# Fuente.net
KiCad netlist of a schematic drawn in Altium Designer
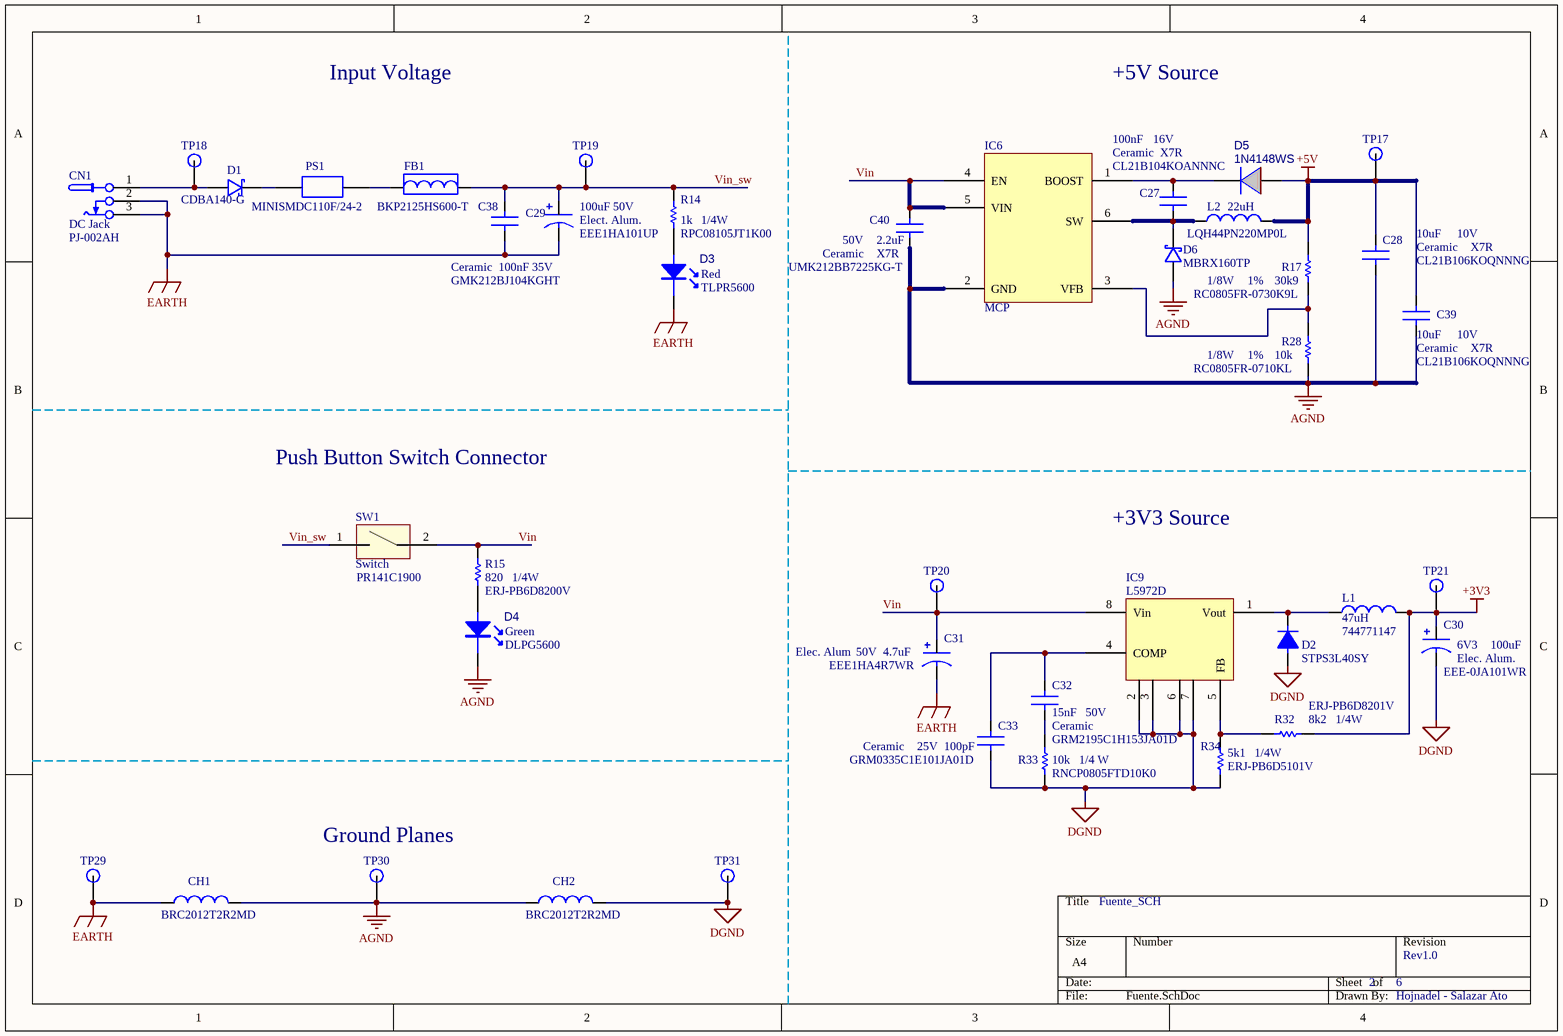
[diagram p0: Fuente.SchDoc]

(export (version "E")
  (design (tool "Eeschema 10.0.6"))
  (components
    (comp (ref "C27")
      (value "100nF 16V X7R")
      (footprint "C_0805")
      (description "Capacitor")
      (fields
        (field (name "C") "100nF")
        (field (name "V") "16V")
        (field (name "PART NUMBER") "CL21B104KOANNNC")
        (field (name "MATERIAL") "Ceramic")
        (field (name "COEF. TERM.") "X7R")
      )
      (libsource (lib "TDII_Lib_V2") (part "Cap1"))
    )
    (comp (ref "C28")
      (value "10uF 10V X7R")
      (footprint "C_0805")
      (description "Capacitor")
      (fields
        (field (name "C") "10uF")
        (field (name "V") "10V")
        (field (name "PART NUMBER") "CL21B106KOQNNNG")
        (field (name "MATERIAL") "Ceramic")
        (field (name "COEF. TERM.") "X7R")
      )
      (libsource (lib "TDII_Lib_V2") (part "Cap1"))
    )
    (comp (ref "C29")
      (value "100uF 50V ElecAlum")
      (footprint "C_AE10083X105M")
      (description "Capacitor")
      (fields
        (field (name "C") "100uF")
        (field (name "V") "50V")
        (field (name "MATERIAL") "Elect. Alum.")
        (field (name "PART NUMBER") "EEE1HA101UP")
      )
      (libsource (lib "TDII_Lib_V2") (part "Cap_Elec"))
    )
    (comp (ref "C30")
      (value "100uF 6V3 ElecAlum")
      (footprint "C_AE6553X54M")
      (description "Capacitor")
      (fields
        (field (name "C") "100uF")
        (field (name "V") "6V3")
        (field (name "MATERIAL") "Elec. Alum.")
        (field (name "PART NUMBER") "EEE-0JA101WR")
      )
      (libsource (lib "TDII_Lib_V2") (part "Cap_Elec"))
    )
    (comp (ref "C31")
      (value "4.7uF 50V ElecAlum")
      (footprint "C_AE6553X54M")
      (description "Capacitor")
      (fields
        (field (name "C") "4.7uF")
        (field (name "V") "50V")
        (field (name "MATERIAL") "Elec. Alum")
        (field (name "PART NUMBER") "EEE1HA4R7WR")
      )
      (libsource (lib "TDII_Lib_V2") (part "Cap_Elec"))
    )
    (comp (ref "C32")
      (value "15nF 50V Ceramic")
      (footprint "C_0805")
      (description "Capacitor")
      (fields
        (field (name "C") "15nF")
        (field (name "V") "50V")
        (field (name "PART NUMBER") "GRM2195C1H153JA01D")
        (field (name "MATERIAL") "Ceramic")
      )
      (libsource (lib "TDII_Lib_V2") (part "Cap1"))
    )
    (comp (ref "C33")
      (value "100pF 25V Ceramic")
      (footprint "C_0805")
      (description "Capacitor")
      (fields
        (field (name "C") "100pF")
        (field (name "V") "25V")
        (field (name "PART NUMBER") "GRM0335C1E101JA01D")
        (field (name "MATERIAL") "Ceramic")
      )
      (libsource (lib "TDII_Lib_V2") (part "Cap1"))
    )
    (comp (ref "C38")
      (value "100nF 35V Ceramic")
      (footprint "C_0805")
      (description "Capacitor")
      (fields
        (field (name "C") "100nF")
        (field (name "V") "35V")
        (field (name "PART NUMBER") "GMK212BJ104KGHT")
        (field (name "MATERIAL") "Ceramic")
      )
      (libsource (lib "TDII_Lib_V2") (part "Cap1"))
    )
    (comp (ref "C39")
      (value "10uF 10V X7R")
      (footprint "C_0805")
      (description "Capacitor")
      (fields
        (field (name "C") "10uF")
        (field (name "V") "10V")
        (field (name "PART NUMBER") "CL21B106KOQNNNG")
        (field (name "MATERIAL") "Ceramic")
        (field (name "COEF. TERM.") "X7R")
      )
      (libsource (lib "TDII_Lib_V2") (part "Cap1"))
    )
    (comp (ref "C40")
      (value "2.2uF 50V X7R")
      (footprint "C_0805")
      (description "Capacitor")
      (fields
        (field (name "C") "2.2uF")
        (field (name "V") "50V")
        (field (name "PART NUMBER") "UMK212BB7225KG-T")
        (field (name "MATERIAL") "Ceramic")
        (field (name "TEMP. COEF.") "X7R")
      )
      (libsource (lib "TDII_Lib_V2") (part "Cap1"))
    )
    (comp (ref "CH1")
      (value "Choke")
      (footprint "I_CHOQUE_DFN")
      (fields (field (name "PART NUMBER") "BRC2012T2R2MD"))
      (libsource (lib "TDII_Lib_V2") (part "Choke"))
    )
    (comp (ref "CH2")
      (value "Choke")
      (footprint "I_CHOQUE_DFN")
      (fields (field (name "PART NUMBER") "BRC2012T2R2MD"))
      (libsource (lib "TDII_Lib_V2") (part "Choke"))
    )
    (comp (ref "CN1")
      (value "DC Jack")
      (footprint "Jack_PJ002A")
      (description "Connector")
      (fields (field (name "PART NUMBER") "PJ-002AH"))
      (libsource (lib "TDII_Lib_V2") (part "Barrel_jack"))
    )
    (comp (ref "D1")
      (value "CDBA140-G")
      (footprint "D_DO-214AC_Schottky")
      (description "Diodo Schottky")
      (libsource (lib "TDII_Lib_V2") (part "Diodo_Schottky"))
    )
    (comp (ref "D2")
      (value "STPS3L40")
      (footprint "D_M6959X25N")
      (description "Diode")
      (fields (field (name "PART NUMBER") "STPS3L40SY"))
      (libsource (lib "LituLib") (part "DIODO"))
    )
    (comp (ref "D3")
      (value "LED")
      (footprint "Led_TH")
      (fields (field (name "COLOR") "Red") (field (name "PART NUMBER") "TLPR5600"))
      (libsource (lib "TDII_Lib_V2") (part "LED"))
    )
    (comp (ref "D4")
      (value "LED")
      (footprint "Led_TH")
      (fields (field (name "PART NUMBER") "DLPG5600") (field (name "COLOR") "Green"))
      (libsource (lib "TDII_Lib_V2") (part "LED"))
    )
    (comp (ref "D5")
      (value "1N4148WS")
      (footprint "1N4148WS")
      (description "Diode signal")
      (libsource (lib "TDII_Lib_V2") (part "DIODO"))
    )
    (comp (ref "D6")
      (value "MBRX160TP")
      (footprint "SOD_123")
      (libsource (lib "TDII_Lib_V2") (part "Diodo_Schottky"))
    )
    (comp (ref "FB1")
      (value "Ferrite Bead")
      (footprint "Ferrite_bead")
      (fields (field (name "PART NUMBER") "BKP2125HS600-T"))
      (libsource (lib "TDII_Lib_V2") (part "Ferrite Bead"))
    )
    (comp (ref "IC6")
      (value "MCP")
      (footprint "SOT23_6P")
      (description "Switching Source")
      (libsource (lib "TDII_Lib_V2") (part "Sw Source"))
    )
    (comp (ref "IC9")
      (value "L5972D")
      (footprint "SO8")
      (description "Fuente Switching")
      (fields (field (name "PART NUMBER") "L5972D013TR"))
      (libsource (lib "TDII_Lib_V2") (part "L5972D"))
    )
    (comp (ref "L1")
      (value "47uH")
      (footprint "I_P128122X60N")
      (description "Inductor")
      (fields (field (name "PART NUMBER") "744771147") (field (name "PUBLISHER") "Altium Limited"))
      (libsource (lib "LituLib") (part "Inductor"))
    )
    (comp (ref "L2")
      (value "LQH44PN220MP0L")
      (footprint "VLCF5028")
      (description "Inductor")
      (fields (field (name "ALTIUM_VALUE") "22uH") (field (name "PUBLISHER") "Altium Limited"))
      (libsource (lib "LituLib") (part "Inductor"))
    )
    (comp (ref "PS1")
      (value "Polyswitch")
      (footprint "POLISWITCH_1")
      (description "Polishwitch")
      (fields (field (name "PART NUMBER") "MINISMDC110F/24-2"))
      (libsource (lib "TDII_Lib_V2") (part "Poliswitch"))
    )
    (comp (ref "R14")
      (value "1k")
      (footprint "R_0805")
      (description "Resistor")
      (fields
        (field (name "POTENCIA") "1/4W")
        (field (name "PART NUMBER") "RPC08105JT1K00")
        (field (name "Comment") "Res1")
      )
      (libsource (lib "TDII_Lib_V2") (part "Res1"))
    )
    (comp (ref "R15")
      (value "820")
      (footprint "R_0805")
      (description "Resistor")
      (fields
        (field (name "TOLERANCE") "5%")
        (field (name "POTENCIA") "1/4W")
        (field (name "PART NUMBER") "ERJ-PB6D8200V")
        (field (name "Comment") "Res1")
      )
      (libsource (lib "TDII_Lib_V2") (part "Res1"))
    )
    (comp (ref "R17")
      (value "30k9")
      (footprint "R_0805")
      (description "Resistor")
      (fields
        (field (name "TOLERANCE") "1%")
        (field (name "POWER") "1/8W")
        (field (name "PART NUMBER") "RC0805FR-0730K9L")
        (field (name "Comment") "30k9 1%")
      )
      (libsource (lib "TDII_Lib_V2") (part "Res1"))
    )
    (comp (ref "R28")
      (value "10k")
      (footprint "R_0805")
      (description "Resistor")
      (fields
        (field (name "TOLERANCE") "1%")
        (field (name "POWER") "1/8W")
        (field (name "PART NUMBER") "RC0805FR-0710KL")
        (field (name "Comment") "30k9 1%")
      )
      (libsource (lib "TDII_Lib_V2") (part "Res1"))
    )
    (comp (ref "R32")
      (value "8k2")
      (footprint "R_0805")
      (description "Resistor")
      (fields
        (field (name "PART NUMBER") "ERJ-PB6D8201V")
        (field (name "POWER") "1/4W")
        (field (name "Comment") "8k2 1/4W")
      )
      (libsource (lib "TDII_Lib_V2") (part "Res1"))
    )
    (comp (ref "R33")
      (value "10k")
      (footprint "R_0805")
      (description "Resistor")
      (fields
        (field (name "PART NUMBER") "RNCP0805FTD10K0")
        (field (name "POWER") "1/4 W")
        (field (name "Comment") "10k 1/4W")
      )
      (libsource (lib "TDII_Lib_V2") (part "Res1"))
    )
    (comp (ref "R34")
      (value "5k1")
      (footprint "R_0805")
      (description "Resistor")
      (fields
        (field (name "PART NUMBER") "ERJ-PB6D5101V")
        (field (name "POWER") "1/4W")
        (field (name "Comment") "5k1 1/4W")
      )
      (libsource (lib "TDII_Lib_V2") (part "Res1"))
    )
    (comp (ref "SW1")
      (value "Switch")
      (footprint "BORNERA_2X5MM")
      (fields (field (name "PART NUMBER") "PR141C1900"))
      (libsource (lib "LituLib") (part "SW"))
    )
    (comp (ref "TP17")
      (value "TP")
      (footprint "TP")
      (description "Test Point")
      (libsource (lib "LituLib") (part "Test Point"))
    )
    (comp (ref "TP18")
      (value "TP")
      (footprint "TP")
      (description "Test Point")
      (libsource (lib "LituLib") (part "Test Point"))
    )
    (comp (ref "TP19")
      (value "TP")
      (footprint "TP")
      (description "Test Point")
      (libsource (lib "LituLib") (part "Test Point"))
    )
    (comp (ref "TP20")
      (value "TP")
      (footprint "TP")
      (description "Test Point")
      (libsource (lib "LituLib") (part "Test Point"))
    )
    (comp (ref "TP21")
      (value "TP")
      (footprint "TP")
      (description "Test Point")
      (libsource (lib "LituLib") (part "Test Point"))
    )
    (comp (ref "TP29")
      (value "TP")
      (footprint "TP")
      (description "Test Point")
      (libsource (lib "LituLib") (part "Test Point"))
    )
    (comp (ref "TP30")
      (value "TP")
      (footprint "TP")
      (description "Test Point")
      (libsource (lib "LituLib") (part "Test Point"))
    )
    (comp (ref "TP31")
      (value "TP")
      (footprint "TP")
      (description "Test Point")
      (libsource (lib "LituLib") (part "Test Point"))
    )
  )
  (nets
    (net (code "1") (name "+3V3") (class "Default")
      (node (ref "C30") (pin "1") (pinfunction "1_1") (pintype "passive"))
      (node (ref "L1") (pin "2") (pinfunction "2_2") (pintype "passive"))
      (node (ref "R32") (pin "1") (pinfunction "1_1") (pintype "passive"))
      (node (ref "TP21") (pin "1") (pinfunction "1_1") (pintype "passive"))
    )
    (net (code "2") (name "+5V") (class "Default")
      (node (ref "C28") (pin "1") (pinfunction "1_1") (pintype "passive"))
      (node (ref "C39") (pin "1") (pinfunction "1_1") (pintype "passive"))
      (node (ref "D5") (pin "1") (pinfunction "A_1") (pintype "passive"))
      (node (ref "L2") (pin "2") (pinfunction "2_2") (pintype "passive"))
      (node (ref "R17") (pin "2") (pinfunction "2_2") (pintype "passive"))
      (node (ref "TP17") (pin "1") (pinfunction "1_1") (pintype "passive"))
    )
    (net (code "3") (name "/Vin") (class "Default")
      (node (ref "C31") (pin "1") (pinfunction "1_1") (pintype "passive"))
      (node (ref "C40") (pin "1") (pinfunction "1_1") (pintype "passive"))
      (node (ref "IC6") (pin "4") (pinfunction "EN_4") (pintype "passive"))
      (node (ref "IC6") (pin "5") (pinfunction "VIN_5") (pintype "passive"))
      (node (ref "IC9") (pin "8") (pinfunction "Vin_8") (pintype "passive"))
      (node (ref "R15") (pin "2") (pinfunction "2_2") (pintype "passive"))
      (node (ref "SW1") (pin "2") (pinfunction "2_2") (pintype "passive"))
      (node (ref "TP20") (pin "1") (pinfunction "1_1") (pintype "passive"))
    )
    (net (code "4") (name "/Vin_sw") (class "Default")
      (node (ref "C29") (pin "1") (pinfunction "1_1") (pintype "passive"))
      (node (ref "C38") (pin "1") (pinfunction "1_1") (pintype "passive"))
      (node (ref "FB1") (pin "2") (pinfunction "2_2") (pintype "passive"))
      (node (ref "R14") (pin "1") (pinfunction "1_1") (pintype "passive"))
      (node (ref "SW1") (pin "1") (pinfunction "1_1") (pintype "passive"))
      (node (ref "TP19") (pin "1") (pinfunction "1_1") (pintype "passive"))
    )
    (net (code "5") (name "AGND") (class "Default")
      (node (ref "C28") (pin "2") (pinfunction "2_2") (pintype "passive"))
      (node (ref "C39") (pin "2") (pinfunction "2_2") (pintype "passive"))
      (node (ref "C40") (pin "2") (pinfunction "2_2") (pintype "passive"))
      (node (ref "CH1") (pin "2") (pinfunction "2_2") (pintype "passive"))
      (node (ref "CH2") (pin "1") (pinfunction "1_1") (pintype "passive"))
      (node (ref "D4") (pin "2") (pinfunction "2_2") (pintype "passive"))
      (node (ref "D6") (pin "1") (pinfunction "A_1") (pintype "passive"))
      (node (ref "IC6") (pin "2") (pinfunction "GND_2") (pintype "passive"))
      (node (ref "R28") (pin "1") (pinfunction "1_1") (pintype "passive"))
      (node (ref "TP30") (pin "1") (pinfunction "1_1") (pintype "passive"))
    )
    (net (code "6") (name "DGND") (class "Default")
      (node (ref "C30") (pin "2") (pinfunction "2_2") (pintype "passive"))
      (node (ref "C33") (pin "2") (pinfunction "2_2") (pintype "passive"))
      (node (ref "CH2") (pin "2") (pinfunction "2_2") (pintype "passive"))
      (node (ref "D2") (pin "1") (pinfunction "1_1") (pintype "passive"))
      (node (ref "IC9") (pin "2") (pinfunction "GND_2") (pintype "passive"))
      (node (ref "IC9") (pin "3") (pinfunction "GND_3") (pintype "passive"))
      (node (ref "IC9") (pin "6") (pinfunction "GND_6") (pintype "passive"))
      (node (ref "IC9") (pin "7") (pinfunction "GND_7") (pintype "passive"))
      (node (ref "R33") (pin "1") (pinfunction "1_1") (pintype "passive"))
      (node (ref "R34") (pin "1") (pinfunction "1_1") (pintype "passive"))
      (node (ref "TP31") (pin "1") (pinfunction "1_1") (pintype "passive"))
    )
    (net (code "7") (name "EARTH") (class "Default")
      (node (ref "C29") (pin "2") (pinfunction "2_2") (pintype "passive"))
      (node (ref "C31") (pin "2") (pinfunction "2_2") (pintype "passive"))
      (node (ref "C38") (pin "2") (pinfunction "2_2") (pintype "passive"))
      (node (ref "CH1") (pin "1") (pinfunction "1_1") (pintype "passive"))
      (node (ref "CN1") (pin "2") (pinfunction "2_2") (pintype "passive"))
      (node (ref "CN1") (pin "3") (pinfunction "3_3") (pintype "passive"))
      (node (ref "D3") (pin "2") (pinfunction "2_2") (pintype "passive"))
      (node (ref "TP29") (pin "1") (pinfunction "1_1") (pintype "passive"))
    )
    (net (code "8") (name "Net-(C32-Pad2)") (class "Default")
      (node (ref "C32") (pin "2") (pinfunction "2_2") (pintype "passive"))
      (node (ref "R33") (pin "2") (pinfunction "2_2") (pintype "passive"))
    )
    (net (code "9") (name "Net-(D1-A)") (class "Default")
      (node (ref "CN1") (pin "1") (pinfunction "1_1") (pintype "passive"))
      (node (ref "D1") (pin "1") (pinfunction "A_1") (pintype "passive"))
      (node (ref "TP18") (pin "1") (pinfunction "1_1") (pintype "passive"))
    )
    (net (code "10") (name "Net-(D1-K)") (class "Default")
      (node (ref "D1") (pin "2") (pinfunction "K_2") (pintype "passive"))
      (node (ref "PS1") (pin "1") (pinfunction "1_1") (pintype "passive"))
    )
    (net (code "11") (name "Net-(D3-Pad1)") (class "Default")
      (node (ref "D3") (pin "1") (pinfunction "1_1") (pintype "passive"))
      (node (ref "R14") (pin "2") (pinfunction "2_2") (pintype "passive"))
    )
    (net (code "12") (name "Net-(D4-Pad1)") (class "Default")
      (node (ref "D4") (pin "1") (pinfunction "1_1") (pintype "passive"))
      (node (ref "R15") (pin "1") (pinfunction "1_1") (pintype "passive"))
    )
    (net (code "13") (name "Net-(D5-K)") (class "Default")
      (node (ref "C27") (pin "1") (pinfunction "1_1") (pintype "passive"))
      (node (ref "D5") (pin "2") (pinfunction "K_2") (pintype "passive"))
      (node (ref "IC6") (pin "1") (pinfunction "BOOST_1") (pintype "passive"))
    )
    (net (code "14") (name "Net-(D6-K)") (class "Default")
      (node (ref "C27") (pin "2") (pinfunction "2_2") (pintype "passive"))
      (node (ref "D6") (pin "2") (pinfunction "K_2") (pintype "passive"))
      (node (ref "IC6") (pin "6") (pinfunction "SW_6") (pintype "passive"))
      (node (ref "L2") (pin "1") (pinfunction "1_1") (pintype "passive"))
    )
    (net (code "15") (name "Net-(FB1-Pad1)") (class "Default")
      (node (ref "FB1") (pin "1") (pinfunction "1_1") (pintype "passive"))
      (node (ref "PS1") (pin "2") (pinfunction "2_2") (pintype "passive"))
    )
    (net (code "16") (name "Net-(IC6-VFB)") (class "Default")
      (node (ref "IC6") (pin "3") (pinfunction "VFB_3") (pintype "passive"))
      (node (ref "R17") (pin "1") (pinfunction "1_1") (pintype "passive"))
      (node (ref "R28") (pin "2") (pinfunction "2_2") (pintype "passive"))
    )
    (net (code "17") (name "Net-(IC9-COMP)") (class "Default")
      (node (ref "C32") (pin "1") (pinfunction "1_1") (pintype "passive"))
      (node (ref "C33") (pin "1") (pinfunction "1_1") (pintype "passive"))
      (node (ref "IC9") (pin "4") (pinfunction "COMP_4") (pintype "passive"))
    )
    (net (code "18") (name "Net-(IC9-FB)") (class "Default")
      (node (ref "IC9") (pin "5") (pinfunction "FB_5") (pintype "passive"))
      (node (ref "R32") (pin "2") (pinfunction "2_2") (pintype "passive"))
      (node (ref "R34") (pin "2") (pinfunction "2_2") (pintype "passive"))
    )
    (net (code "19") (name "Net-(IC9-Vout)") (class "Default")
      (node (ref "D2") (pin "2") (pinfunction "2_2") (pintype "passive"))
      (node (ref "IC9") (pin "1") (pinfunction "Vout_1") (pintype "passive"))
      (node (ref "L1") (pin "1") (pinfunction "1_1") (pintype "passive"))
    )
  )
)
